# Tra_doantotnghiep.net
KiCad netlist of a schematic drawn in Altium Designer
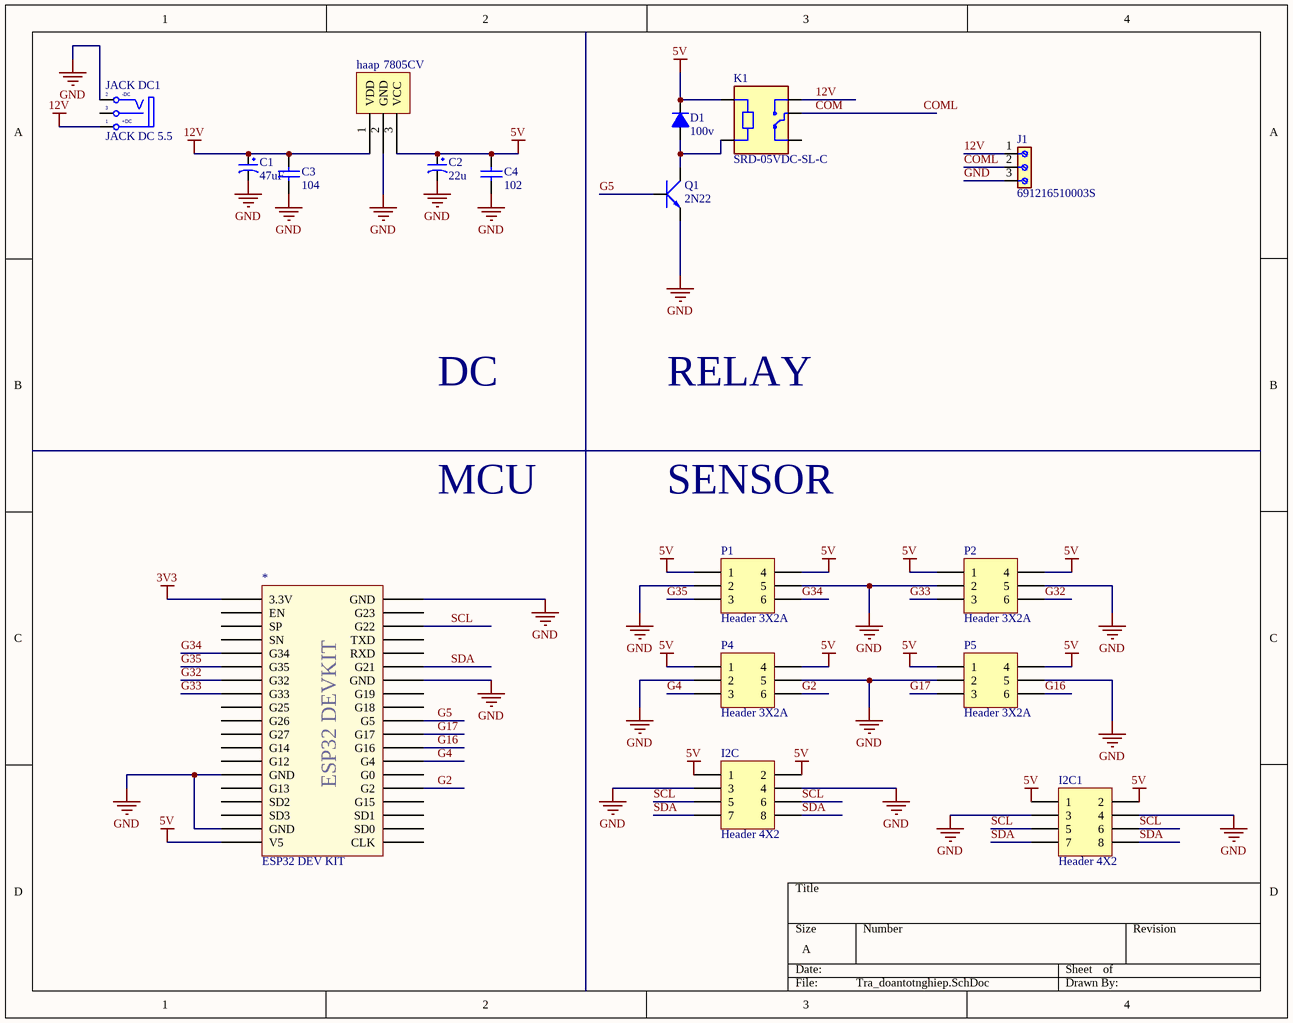
[diagram p0: Tra_doantotnghiep.SchDoc]

(export (version "E")
  (design (tool "Eeschema 10.0.6"))
  (components
    (comp (ref "*")
      (value "ESP32 DEV KIT")
      (footprint "ESP32 DEVKIT")
      (libsource (lib "Altium_Lib_by_KhueNguyenCreator") (part "ESP32 DEV KIT"))
    )
    (comp (ref "C1")
      (value "47uF")
      (footprint "tu hoa 5mm")
      (description "Cắm")
      (libsource (lib "Altium_Lib_by_KhueNguyenCreator") (part "Tu Hoa 47uF 16V 5x10"))
    )
    (comp (ref "C2")
      (value "22u")
      (footprint "tu hoa 5mm")
      (description "Cắm")
      (libsource (lib "Altium_Lib_by_KhueNguyenCreator") (part "Tu Hoa 47uF 16V 5x10"))
    )
    (comp (ref "C3")
      (value "104")
      (footprint "tu gom")
      (description "Cắm")
      (libsource (lib "Altium_Lib_by_KhueNguyenCreator") (part "Tu gom 104 50V"))
    )
    (comp (ref "C4")
      (value "102")
      (footprint "tu gom")
      (description "Cắm")
      (libsource (lib "Altium_Lib_by_KhueNguyenCreator") (part "Tu gom 102 50V"))
    )
    (comp (ref "D1")
      (value "100v")
      (footprint "DIODE 1A")
      (description "Cắm")
      (libsource (lib "Altium_Lib_by_KhueNguyenCreator") (part "Diode 1N4007"))
    )
    (comp (ref "haap") (value "7805CV") (footprint "TO-220-3") (libsource (lib "TV") (part "7805CV")))
    (comp (ref "I2C")
      (value "Header 4X2")
      (footprint "HDR2X4")
      (description "Header, 4-Pin, Dual row")
      (fields (field (name "PUBLISHER") "Altium Limited"))
      (libsource (lib "Miscellaneous Connectors") (part "Header 4X2"))
    )
    (comp (ref "I2C1")
      (value "Header 4X2")
      (footprint "HDR2X4")
      (description "Header, 4-Pin, Dual row")
      (fields (field (name "PUBLISHER") "Altium Limited"))
      (libsource (lib "Miscellaneous Connectors") (part "Header 4X2"))
    )
    (comp (ref "J1")
      (value "691216510003S")
      (footprint "691216510003S")
      (description "5.08 MM TERMINAL BLOCK;")
      (fields (field (name "MF") "WÃ¼rth Elektronik"))
      (libsource (lib "TV") (part "691216510003S"))
    )
    (comp (ref "JACK DC1")
      (value "JACK DC 5.5")
      (footprint "JACK DC 5.5")
      (libsource (lib "Altium_Lib_by_KhueNguyenCreator") (part "JACK DC 5.5"))
    )
    (comp (ref "K1")
      (value "SRD-05VDC-SL-C")
      (footprint "RELAY_SRD-05VDC-SL-C")
      (fields (field (name "MF") "Songle Relay"))
      (libsource (lib "TV") (part "SRD-05VDC-SL-C"))
    )
    (comp (ref "P1")
      (value "Header 3X2A")
      (footprint "HDR2X3_CEN")
      (description "Header, 3-Pin, Dual row")
      (fields (field (name "PUBLISHER") "Altium Limited"))
      (libsource (lib "Miscellaneous Connectors") (part "Header 3X2A"))
    )
    (comp (ref "P2")
      (value "Header 3X2A")
      (footprint "HDR2X3_CEN")
      (description "Header, 3-Pin, Dual row")
      (fields (field (name "PUBLISHER") "Altium Limited"))
      (libsource (lib "Miscellaneous Connectors") (part "Header 3X2A"))
    )
    (comp (ref "P4")
      (value "Header 3X2A")
      (footprint "HDR2X3_CEN")
      (description "Header, 3-Pin, Dual row")
      (fields (field (name "PUBLISHER") "Altium Limited"))
      (libsource (lib "Miscellaneous Connectors") (part "Header 3X2A"))
    )
    (comp (ref "P5")
      (value "Header 3X2A")
      (footprint "HDR2X3_CEN")
      (description "Header, 3-Pin, Dual row")
      (fields (field (name "PUBLISHER") "Altium Limited"))
      (libsource (lib "Miscellaneous Connectors") (part "Header 3X2A"))
    )
    (comp (ref "Q1")
      (value "2N22")
      (footprint "TO92")
      (description "NPN transistor EBC")
      (libsource (lib "Altium_Lib_by_KhueNguyenCreator") (part "Trans 2N3904"))
    )
  )
  (nets
    (net (code "1") (name "/COM") (class "Default")
      (node (ref "J1") (pin "2") (pinfunction "2_2") (pintype "passive"))
      (node (ref "K1") (pin "COM") (pinfunction "COM_COM") (pintype "passive"))
    )
    (net (code "2") (name "/G2") (class "Default")
      (node (ref "*") (pin "24") (pinfunction "G2_24") (pintype "passive"))
      (node (ref "P4") (pin "6") (pinfunction "6_6") (pintype "passive"))
    )
    (net (code "3") (name "/G4") (class "Default")
      (node (ref "*") (pin "26") (pinfunction "G4_26") (pintype "passive"))
      (node (ref "P4") (pin "3") (pinfunction "3_3") (pintype "passive"))
    )
    (net (code "4") (name "/G5") (class "Default")
      (node (ref "*") (pin "29") (pinfunction "G5_29") (pintype "passive"))
      (node (ref "Q1") (pin "2") (pinfunction "B_2") (pintype "passive"))
    )
    (net (code "5") (name "/G16") (class "Default")
      (node (ref "*") (pin "27") (pinfunction "G16_27") (pintype "passive"))
      (node (ref "P5") (pin "6") (pinfunction "6_6") (pintype "passive"))
    )
    (net (code "6") (name "/G17") (class "Default")
      (node (ref "*") (pin "28") (pinfunction "G17_28") (pintype "passive"))
      (node (ref "P5") (pin "3") (pinfunction "3_3") (pintype "passive"))
    )
    (net (code "7") (name "/G32") (class "Default")
      (node (ref "*") (pin "7") (pinfunction "G32_7") (pintype "passive"))
      (node (ref "P2") (pin "6") (pinfunction "6_6") (pintype "passive"))
    )
    (net (code "8") (name "/G33") (class "Default")
      (node (ref "*") (pin "8") (pinfunction "G33_8") (pintype "passive"))
      (node (ref "P2") (pin "3") (pinfunction "3_3") (pintype "passive"))
    )
    (net (code "9") (name "/G34") (class "Default")
      (node (ref "*") (pin "5") (pinfunction "G34_5") (pintype "passive"))
      (node (ref "P1") (pin "6") (pinfunction "6_6") (pintype "passive"))
    )
    (net (code "10") (name "/G35") (class "Default")
      (node (ref "*") (pin "6") (pinfunction "G35_6") (pintype "passive"))
      (node (ref "P1") (pin "3") (pinfunction "3_3") (pintype "passive"))
    )
    (net (code "11") (name "/SCL") (class "Default")
      (node (ref "*") (pin "36") (pinfunction "G22_36") (pintype "passive"))
      (node (ref "I2C") (pin "5") (pinfunction "5_5") (pintype "passive"))
      (node (ref "I2C") (pin "6") (pinfunction "6_6") (pintype "passive"))
      (node (ref "I2C1") (pin "5") (pinfunction "5_5") (pintype "passive"))
      (node (ref "I2C1") (pin "6") (pinfunction "6_6") (pintype "passive"))
    )
    (net (code "12") (name "/SDA") (class "Default")
      (node (ref "*") (pin "33") (pinfunction "G21_33") (pintype "passive"))
      (node (ref "I2C") (pin "7") (pinfunction "7_7") (pintype "passive"))
      (node (ref "I2C") (pin "8") (pinfunction "8_8") (pintype "passive"))
      (node (ref "I2C1") (pin "7") (pinfunction "7_7") (pintype "passive"))
      (node (ref "I2C1") (pin "8") (pinfunction "8_8") (pintype "passive"))
    )
    (net (code "13") (name "3V3") (class "Default")
      (node (ref "*") (pin "1") (pinfunction "3.3V_1") (pintype "passive"))
    )
    (net (code "14") (name "5V") (class "Default")
      (node (ref "*") (pin "19") (pinfunction "V5_19") (pintype "passive"))
      (node (ref "C2") (pin "1") (pinfunction "1_1") (pintype "passive"))
      (node (ref "C4") (pin "1") (pinfunction "1_1") (pintype "passive"))
      (node (ref "D1") (pin "2") (pinfunction "K_2") (pintype "passive"))
      (node (ref "I2C") (pin "1") (pinfunction "1_1") (pintype "passive"))
      (node (ref "I2C") (pin "2") (pinfunction "2_2") (pintype "passive"))
      (node (ref "I2C1") (pin "1") (pinfunction "1_1") (pintype "passive"))
      (node (ref "I2C1") (pin "2") (pinfunction "2_2") (pintype "passive"))
      (node (ref "K1") (pin "A1") (pinfunction "A1_A1") (pintype "passive"))
      (node (ref "P1") (pin "1") (pinfunction "1_1") (pintype "passive"))
      (node (ref "P1") (pin "4") (pinfunction "4_4") (pintype "passive"))
      (node (ref "P2") (pin "1") (pinfunction "1_1") (pintype "passive"))
      (node (ref "P2") (pin "4") (pinfunction "4_4") (pintype "passive"))
      (node (ref "P4") (pin "1") (pinfunction "1_1") (pintype "passive"))
      (node (ref "P4") (pin "4") (pinfunction "4_4") (pintype "passive"))
      (node (ref "P5") (pin "1") (pinfunction "1_1") (pintype "passive"))
      (node (ref "P5") (pin "4") (pinfunction "4_4") (pintype "passive"))
      (node (ref "haap") (pin "3") (pinfunction "VCC_3") (pintype "passive"))
    )
    (net (code "15") (name "12V") (class "Default")
      (node (ref "C1") (pin "1") (pinfunction "1_1") (pintype "passive"))
      (node (ref "C3") (pin "1") (pinfunction "1_1") (pintype "passive"))
      (node (ref "J1") (pin "1") (pinfunction "1_1") (pintype "passive"))
      (node (ref "JACK DC1") (pin "1") (pinfunction "T_1") (pintype "passive"))
      (node (ref "K1") (pin "NO") (pinfunction "NO_NO") (pintype "passive"))
      (node (ref "haap") (pin "1") (pinfunction "VDD_1") (pintype "passive"))
    )
    (net (code "16") (name "GND") (class "Default")
      (node (ref "*") (pin "14") (pinfunction "GND_14") (pintype "passive"))
      (node (ref "*") (pin "18") (pinfunction "GND_18") (pintype "passive"))
      (node (ref "*") (pin "32") (pinfunction "GND_32") (pintype "passive"))
      (node (ref "*") (pin "38") (pinfunction "GND_38") (pintype "passive"))
      (node (ref "C1") (pin "2") (pinfunction "2_2") (pintype "passive"))
      (node (ref "C2") (pin "2") (pinfunction "2_2") (pintype "passive"))
      (node (ref "C3") (pin "2") (pinfunction "2_2") (pintype "passive"))
      (node (ref "C4") (pin "2") (pinfunction "2_2") (pintype "passive"))
      (node (ref "I2C") (pin "3") (pinfunction "3_3") (pintype "passive"))
      (node (ref "I2C") (pin "4") (pinfunction "4_4") (pintype "passive"))
      (node (ref "I2C1") (pin "3") (pinfunction "3_3") (pintype "passive"))
      (node (ref "I2C1") (pin "4") (pinfunction "4_4") (pintype "passive"))
      (node (ref "J1") (pin "3") (pinfunction "3_3") (pintype "passive"))
      (node (ref "JACK DC1") (pin "2") (pinfunction "TN_2") (pintype "passive"))
      (node (ref "P1") (pin "2") (pinfunction "2_2") (pintype "passive"))
      (node (ref "P1") (pin "5") (pinfunction "5_5") (pintype "passive"))
      (node (ref "P2") (pin "2") (pinfunction "2_2") (pintype "passive"))
      (node (ref "P2") (pin "5") (pinfunction "5_5") (pintype "passive"))
      (node (ref "P4") (pin "2") (pinfunction "2_2") (pintype "passive"))
      (node (ref "P4") (pin "5") (pinfunction "5_5") (pintype "passive"))
      (node (ref "P5") (pin "2") (pinfunction "2_2") (pintype "passive"))
      (node (ref "P5") (pin "5") (pinfunction "5_5") (pintype "passive"))
      (node (ref "Q1") (pin "1") (pinfunction "E_1") (pintype "passive"))
      (node (ref "haap") (pin "2") (pinfunction "GND_2") (pintype "passive"))
    )
    (net (code "17") (name "Net-(D1-A)") (class "Default")
      (node (ref "D1") (pin "1") (pinfunction "A_1") (pintype "passive"))
      (node (ref "K1") (pin "A2") (pinfunction "A2_A2") (pintype "passive"))
      (node (ref "Q1") (pin "3") (pinfunction "C_3") (pintype "passive"))
    )
    (net (code "18") (name "unconnected-(*-CLK-Pad20)") (class "Default")
      (node (ref "*") (pin "20") (pinfunction "CLK_20") (pintype "passive"))
    )
    (net (code "19") (name "unconnected-(*-EN-Pad2)") (class "Default")
      (node (ref "*") (pin "2") (pinfunction "EN_2") (pintype "passive"))
    )
    (net (code "20") (name "unconnected-(*-G0-Pad25)") (class "Default")
      (node (ref "*") (pin "25") (pinfunction "G0_25") (pintype "passive"))
    )
    (net (code "21") (name "unconnected-(*-G12-Pad13)") (class "Default")
      (node (ref "*") (pin "13") (pinfunction "G12_13") (pintype "passive"))
    )
    (net (code "22") (name "unconnected-(*-G13-Pad15)") (class "Default")
      (node (ref "*") (pin "15") (pinfunction "G13_15") (pintype "passive"))
    )
    (net (code "23") (name "unconnected-(*-G14-Pad12)") (class "Default")
      (node (ref "*") (pin "12") (pinfunction "G14_12") (pintype "passive"))
    )
    (net (code "24") (name "unconnected-(*-G15-Pad23)") (class "Default")
      (node (ref "*") (pin "23") (pinfunction "G15_23") (pintype "passive"))
    )
    (net (code "25") (name "unconnected-(*-G18-Pad30)") (class "Default")
      (node (ref "*") (pin "30") (pinfunction "G18_30") (pintype "passive"))
    )
    (net (code "26") (name "unconnected-(*-G19-Pad31)") (class "Default")
      (node (ref "*") (pin "31") (pinfunction "G19_31") (pintype "passive"))
    )
    (net (code "27") (name "unconnected-(*-G23-Pad37)") (class "Default")
      (node (ref "*") (pin "37") (pinfunction "G23_37") (pintype "passive"))
    )
    (net (code "28") (name "unconnected-(*-G25-Pad9)") (class "Default")
      (node (ref "*") (pin "9") (pinfunction "G25_9") (pintype "passive"))
    )
    (net (code "29") (name "unconnected-(*-G26-Pad10)") (class "Default")
      (node (ref "*") (pin "10") (pinfunction "G26_10") (pintype "passive"))
    )
    (net (code "30") (name "unconnected-(*-G27-Pad11)") (class "Default")
      (node (ref "*") (pin "11") (pinfunction "G27_11") (pintype "passive"))
    )
    (net (code "31") (name "unconnected-(*-RXD-Pad34)") (class "Default")
      (node (ref "*") (pin "34") (pinfunction "RXD_34") (pintype "passive"))
    )
    (net (code "32") (name "unconnected-(*-SD0-Pad21)") (class "Default")
      (node (ref "*") (pin "21") (pinfunction "SD0_21") (pintype "passive"))
    )
    (net (code "33") (name "unconnected-(*-SD1-Pad22)") (class "Default")
      (node (ref "*") (pin "22") (pinfunction "SD1_22") (pintype "passive"))
    )
    (net (code "34") (name "unconnected-(*-SD2-Pad16)") (class "Default")
      (node (ref "*") (pin "16") (pinfunction "SD2_16") (pintype "passive"))
    )
    (net (code "35") (name "unconnected-(*-SD3-Pad17)") (class "Default")
      (node (ref "*") (pin "17") (pinfunction "SD3_17") (pintype "passive"))
    )
    (net (code "36") (name "unconnected-(*-SN-Pad4)") (class "Default")
      (node (ref "*") (pin "4") (pinfunction "SN_4") (pintype "passive"))
    )
    (net (code "37") (name "unconnected-(*-SP-Pad3)") (class "Default")
      (node (ref "*") (pin "3") (pinfunction "SP_3") (pintype "passive"))
    )
    (net (code "38") (name "unconnected-(*-TXD-Pad35)") (class "Default")
      (node (ref "*") (pin "35") (pinfunction "TXD_35") (pintype "passive"))
    )
    (net (code "39") (name "unconnected-(JACK DC1-S-Pad3)") (class "Default")
      (node (ref "JACK DC1") (pin "3") (pinfunction "S_3") (pintype "power_in"))
    )
    (net (code "40") (name "unconnected-(K1-PadNC)") (class "Default")
      (node (ref "K1") (pin "NC") (pinfunction "NC_NC") (pintype "passive"))
    )
  )
)
